# RP2040-mini_4L.net
KiCad netlist of a schematic drawn in EAGLE
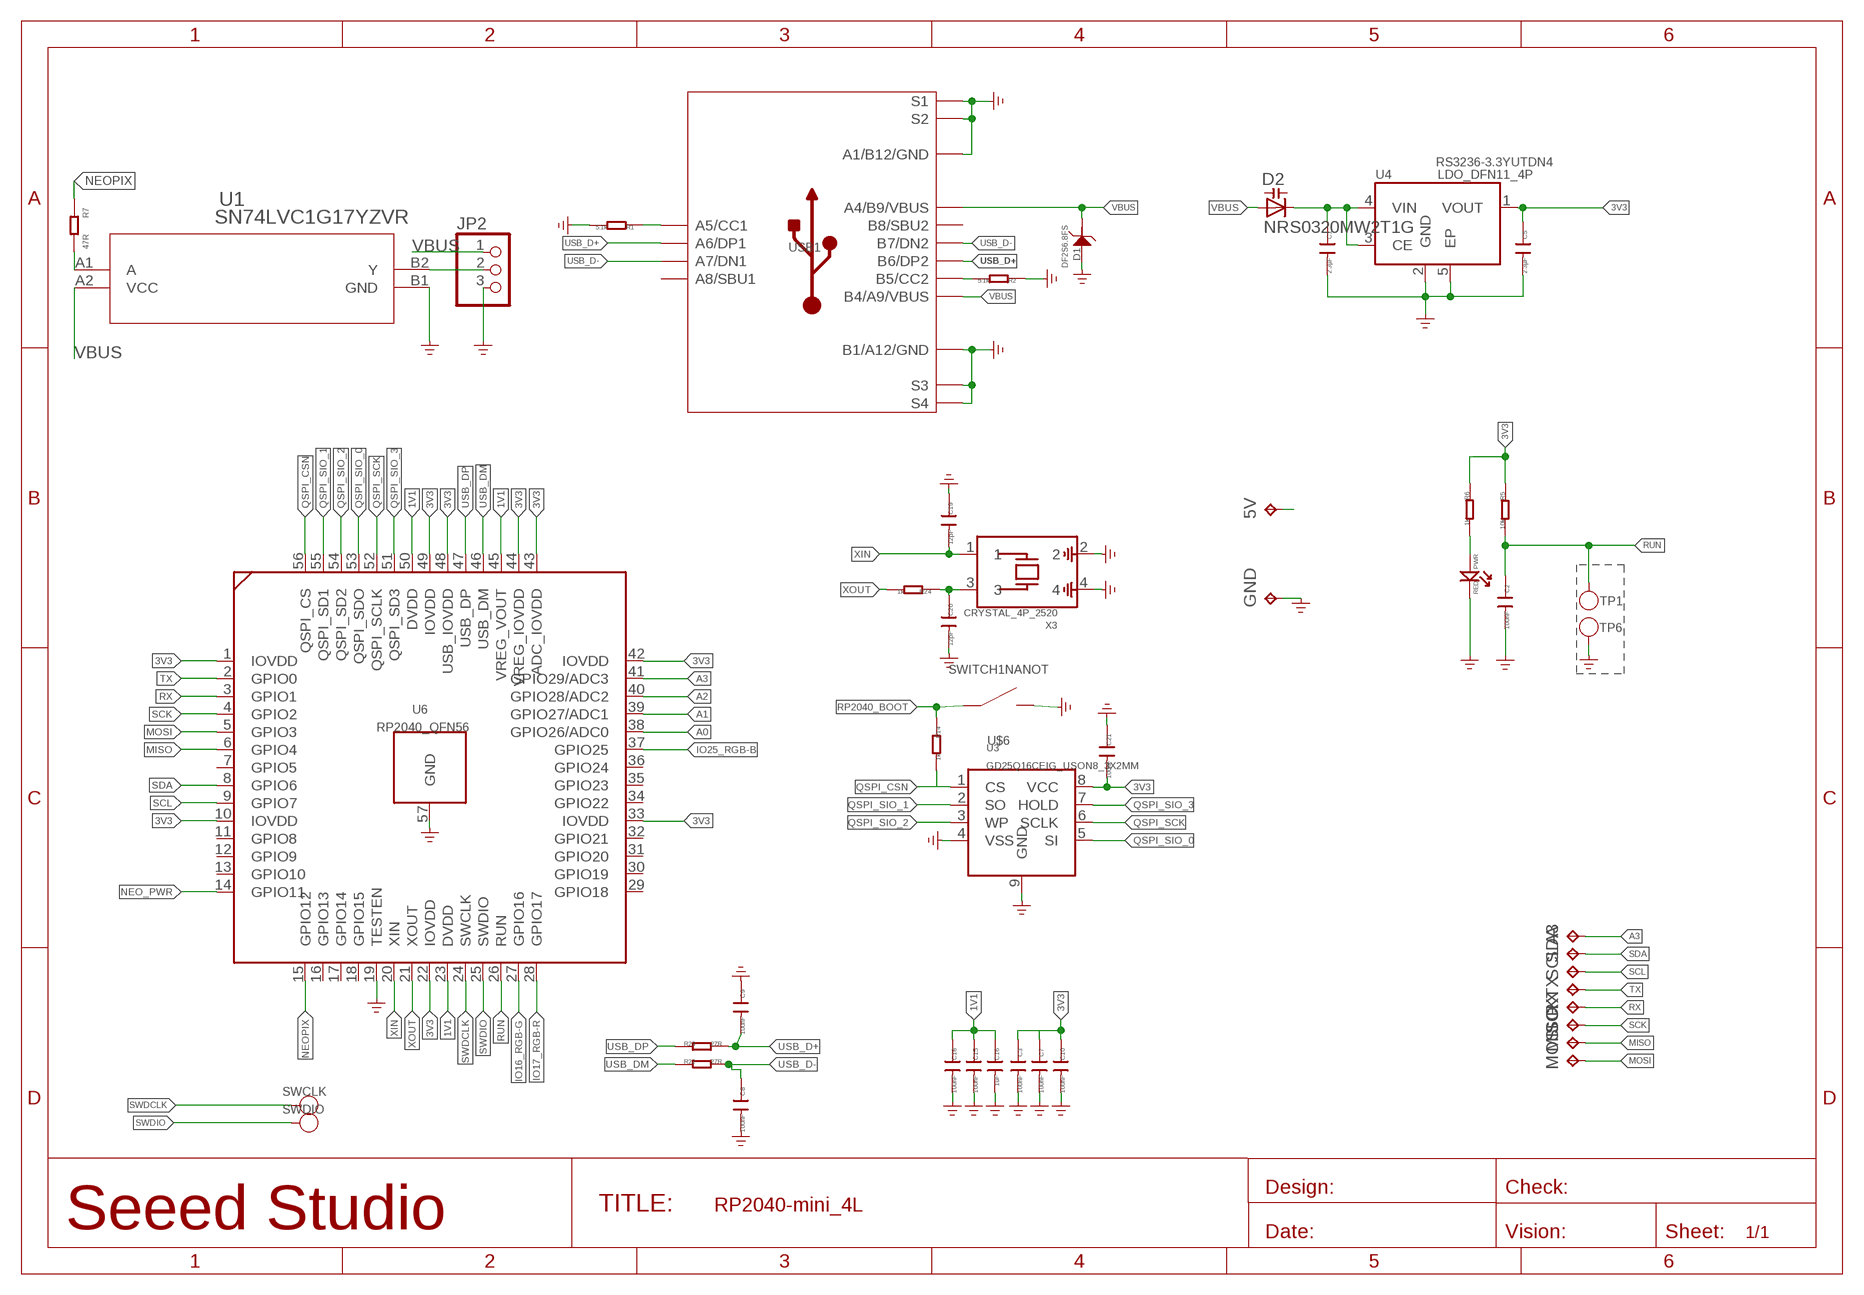
[diagram p0: schematic, sheet 1]

(export (version "E")
  (design (tool "Eeschema 10.0.6"))
  (components
    (comp (ref "5V")
      (value "TPTP09R")
      (footprint "eagle-import:TP09R")
      (libsource (lib "eagle-import") (part "TPTP09R"))
    )
    (comp (ref "A3")
      (value "TPTP07R")
      (footprint "eagle-import:TP07R")
      (libsource (lib "eagle-import") (part "TPTP07R"))
    )
    (comp (ref "C1")
      (value "2.3µF")
      (footprint "eagle-import:0201_NORMAL_NOSILK")
      (libsource (lib "eagle-import") (part "CAP{backslash}0201NNS"))
    )
    (comp (ref "C2")
      (value "100nF")
      (footprint "eagle-import:0201_NORMAL_NOSILK")
      (libsource (lib "eagle-import") (part "CAP{backslash}0201NNS"))
    )
    (comp (ref "C3")
      (value "100nF")
      (footprint "eagle-import:0201_NORMAL_NOSILK")
      (libsource (lib "eagle-import") (part "CAP{backslash}0201NNS"))
    )
    (comp (ref "C5")
      (value "2.3µF")
      (footprint "eagle-import:0201_NORMAL_NOSILK")
      (libsource (lib "eagle-import") (part "CAP{backslash}0201NNS"))
    )
    (comp (ref "C7")
      (value "100nF")
      (footprint "eagle-import:0201_NORMAL_NOSILK")
      (libsource (lib "eagle-import") (part "CAP{backslash}0201NNS"))
    )
    (comp (ref "C8")
      (value "100nF")
      (footprint "eagle-import:0201_NORMAL_NOSILK")
      (libsource (lib "eagle-import") (part "CAP{backslash}0201NNS"))
    )
    (comp (ref "C9")
      (value "100nF")
      (footprint "eagle-import:0201_NORMAL_NOSILK")
      (libsource (lib "eagle-import") (part "CAP{backslash}0201NNS"))
    )
    (comp (ref "C10")
      (value "100nF")
      (footprint "eagle-import:0201_NORMAL_NOSILK")
      (libsource (lib "eagle-import") (part "CAP{backslash}0201NNS"))
    )
    (comp (ref "C15")
      (value "100nF")
      (footprint "eagle-import:0201_NORMAL_NOSILK")
      (libsource (lib "eagle-import") (part "CAP{backslash}0201NNS"))
    )
    (comp (ref "C16")
      (value "1uF")
      (footprint "eagle-import:0201_NORMAL_NOSILK")
      (libsource (lib "eagle-import") (part "CAP{backslash}0201NNS"))
    )
    (comp (ref "C18")
      (value "100nF")
      (footprint "eagle-import:0201_NORMAL_NOSILK")
      (libsource (lib "eagle-import") (part "CAP{backslash}0201NNS"))
    )
    (comp (ref "C19")
      (value "12pF")
      (footprint "eagle-import:0201_NORMAL_NOSILK")
      (libsource (lib "eagle-import") (part "CAP{backslash}0201NNS"))
    )
    (comp (ref "C20")
      (value "12pF")
      (footprint "eagle-import:0201_NORMAL_NOSILK")
      (libsource (lib "eagle-import") (part "CAP{backslash}0201NNS"))
    )
    (comp (ref "C21")
      (value "100nF")
      (footprint "eagle-import:0201_NORMAL_NOSILK")
      (libsource (lib "eagle-import") (part "CAP{backslash}0201NNS"))
    )
    (comp (ref "D1")
      (value "DF2S6.8FS")
      (footprint "eagle-import:SOD-923")
      (libsource (lib "eagle-import") (part "D-ESD-2P'DF2S6.8FS'"))
    )
    (comp (ref "D2")
      (value "NRS0320MW2T1G")
      (footprint "eagle-import:SOD523")
      (libsource (lib "eagle-import") (part "DIODE_CAPACITANCE-SOD523"))
    )
    (comp (ref "GND")
      (value "TPTP09R")
      (footprint "eagle-import:TP09R")
      (libsource (lib "eagle-import") (part "TPTP09R"))
    )
    (comp (ref "JP2")
      (value "PINHD-1X3")
      (footprint "eagle-import:1X03")
      (libsource (lib "eagle-import") (part "PINHD-1X3"))
    )
    (comp (ref "MISO")
      (value "TPTP07R")
      (footprint "eagle-import:TP07R")
      (libsource (lib "eagle-import") (part "TPTP07R"))
    )
    (comp (ref "MOSI")
      (value "TPTP07R")
      (footprint "eagle-import:TP07R")
      (libsource (lib "eagle-import") (part "TPTP07R"))
    )
    (comp (ref "PWR")
      (value "RED")
      (footprint "eagle-import:LED-0402")
      (libsource (lib "eagle-import") (part "LED-0402"))
    )
    (comp (ref "R1")
      (value "5.1k")
      (footprint "eagle-import:R0201")
      (libsource (lib "eagle-import") (part "R-0201"))
    )
    (comp (ref "R2")
      (value "5.1k")
      (footprint "eagle-import:R0201")
      (libsource (lib "eagle-import") (part "R-0201"))
    )
    (comp (ref "R5")
      (value "10k")
      (footprint "eagle-import:R0201")
      (libsource (lib "eagle-import") (part "R-0201"))
    )
    (comp (ref "R6")
      (value "1k")
      (footprint "eagle-import:R0201")
      (libsource (lib "eagle-import") (part "R-0201"))
    )
    (comp (ref "R7")
      (value "47R")
      (footprint "eagle-import:R0201")
      (libsource (lib "eagle-import") (part "RES-0201"))
    )
    (comp (ref "R14")
      (value "1k")
      (footprint "eagle-import:R0201")
      (libsource (lib "eagle-import") (part "R-0201"))
    )
    (comp (ref "R22")
      (value "27R")
      (footprint "eagle-import:R0201")
      (libsource (lib "eagle-import") (part "R-0201"))
    )
    (comp (ref "R23")
      (value "27R")
      (footprint "eagle-import:R0201")
      (libsource (lib "eagle-import") (part "R-0201"))
    )
    (comp (ref "R24")
      (value "1k")
      (footprint "eagle-import:R0201")
      (libsource (lib "eagle-import") (part "R-0201"))
    )
    (comp (ref "RX")
      (value "TPTP07R")
      (footprint "eagle-import:TP07R")
      (libsource (lib "eagle-import") (part "TPTP07R"))
    )
    (comp (ref "SCK")
      (value "TPTP07R")
      (footprint "eagle-import:TP07R")
      (libsource (lib "eagle-import") (part "TPTP07R"))
    )
    (comp (ref "SCL")
      (value "TPTP07R")
      (footprint "eagle-import:TP07R")
      (libsource (lib "eagle-import") (part "TPTP07R"))
    )
    (comp (ref "SDA")
      (value "TPTP07R")
      (footprint "eagle-import:TP07R")
      (libsource (lib "eagle-import") (part "TPTP07R"))
    )
    (comp (ref "SWCLK")
      (value "TEST-POINT-35")
      (footprint "eagle-import:TP_3535")
      (libsource (lib "eagle-import") (part "TEST-POINT-35"))
    )
    (comp (ref "SWDIO")
      (value "TEST-POINT-35")
      (footprint "eagle-import:TP_3535")
      (libsource (lib "eagle-import") (part "TEST-POINT-35"))
    )
    (comp (ref "TP1")
      (value "TEST-POINT-35")
      (footprint "eagle-import:TP_3535")
      (libsource (lib "eagle-import") (part "TEST-POINT-35"))
    )
    (comp (ref "TP6")
      (value "TEST-POINT-35")
      (footprint "eagle-import:TP_3535")
      (libsource (lib "eagle-import") (part "TEST-POINT-35"))
    )
    (comp (ref "TX")
      (value "TPTP07R")
      (footprint "eagle-import:TP07R")
      (libsource (lib "eagle-import") (part "TPTP07R"))
    )
    (comp (ref "U$6")
      (value "SWITCH1NANOT")
      (footprint "eagle-import:NANOT")
      (libsource (lib "eagle-import") (part "SWITCH1NANOT"))
    )
    (comp (ref "U1")
      (value "SN74LVC1G17YZVR")
      (footprint "eagle-import:YZV4")
      (fields (field (name "COPYRIGHT") "Copyright (C) 2024 Ultra Librarian. All rights reserved."))
      (libsource (lib "eagle-import") (part "SN74LVC1G17YZVR"))
    )
    (comp (ref "U3")
      (value "GD25Q16CEIG_USON8_3X2MM")
      (footprint "eagle-import:GD25Q16CEIG_USON8_3X2MM")
      (libsource (lib "eagle-import") (part "GD25Q16CEIG_USON8_3X2MM"))
    )
    (comp (ref "U4")
      (value "LDO_DFN11_4P")
      (footprint "eagle-import:LDO_DFN1_1_4P")
      (libsource (lib "eagle-import") (part "LDO_DFN11_4P"))
    )
    (comp (ref "U6")
      (value "RP2040_QFN56")
      (footprint "eagle-import:RP2040_QFN56")
      (libsource (lib "eagle-import") (part "RP2040_QFN56"))
    )
    (comp (ref "USB1")
      (value "USB2.0-TYPE-C")
      (footprint "eagle-import:USB2.0-TYPE-C")
      (libsource (lib "eagle-import") (part "USB2.0-TYPE-C"))
    )
    (comp (ref "X3")
      (value "CRYSTAL_4P_2520")
      (footprint "eagle-import:CRYSTAL_4P_2520")
      (libsource (lib "eagle-import") (part "CRYSTAL_4P_2520"))
    )
  )
  (nets
    (net (code "1") (name "1V1") (class "Default")
      (node (ref "C15") (pin "1") (pinfunction "1_1") (pintype "passive"))
      (node (ref "C16") (pin "1") (pinfunction "1_1") (pintype "passive"))
      (node (ref "C18") (pin "1") (pinfunction "1_1") (pintype "passive"))
      (node (ref "U6") (pin "23") (pinfunction "DVDD_23") (pintype "bidirectional"))
      (node (ref "U6") (pin "45") (pinfunction "VREG_VOUT_45") (pintype "bidirectional"))
      (node (ref "U6") (pin "50") (pinfunction "DVDD_50") (pintype "bidirectional"))
    )
    (net (code "2") (name "3V3") (class "Default")
      (node (ref "C10") (pin "1") (pinfunction "1_1") (pintype "passive"))
      (node (ref "C21") (pin "2") (pinfunction "2_2") (pintype "passive"))
      (node (ref "C3") (pin "1") (pinfunction "1_1") (pintype "passive"))
      (node (ref "C5") (pin "1") (pinfunction "1_1") (pintype "passive"))
      (node (ref "C7") (pin "1") (pinfunction "1_1") (pintype "passive"))
      (node (ref "R5") (pin "1") (pinfunction "1_1") (pintype "passive"))
      (node (ref "R6") (pin "1") (pinfunction "1_1") (pintype "passive"))
      (node (ref "U3") (pin "8") (pinfunction "VCC_8") (pintype "bidirectional"))
      (node (ref "U4") (pin "1") (pinfunction "VOUT_1") (pintype "bidirectional"))
      (node (ref "U6") (pin "1") (pinfunction "IOVDD_1") (pintype "bidirectional"))
      (node (ref "U6") (pin "10") (pinfunction "IOVDD_10") (pintype "bidirectional"))
      (node (ref "U6") (pin "22") (pinfunction "IOVDD_22") (pintype "bidirectional"))
      (node (ref "U6") (pin "33") (pinfunction "IOVDD_33") (pintype "bidirectional"))
      (node (ref "U6") (pin "42") (pinfunction "IOVDD_42") (pintype "bidirectional"))
      (node (ref "U6") (pin "43") (pinfunction "ADC_IOVDD_43") (pintype "bidirectional"))
      (node (ref "U6") (pin "44") (pinfunction "VREG_IOVDD_44") (pintype "bidirectional"))
      (node (ref "U6") (pin "48") (pinfunction "USB_IOVDD_48") (pintype "bidirectional"))
      (node (ref "U6") (pin "49") (pinfunction "IOVDD_49") (pintype "bidirectional"))
    )
    (net (code "3") (name "A0") (class "Default")
      (node (ref "U6") (pin "38") (pinfunction "GPIO26/ADC0_38") (pintype "bidirectional"))
    )
    (net (code "4") (name "A1") (class "Default")
      (node (ref "U6") (pin "39") (pinfunction "GPIO27/ADC1_39") (pintype "bidirectional"))
    )
    (net (code "5") (name "A2") (class "Default")
      (node (ref "U6") (pin "40") (pinfunction "GPIO28/ADC2_40") (pintype "bidirectional"))
    )
    (net (code "6") (name "A3") (class "Default")
      (node (ref "A3") (pin "TP") (pinfunction "TP_TP") (pintype "input"))
      (node (ref "U6") (pin "41") (pinfunction "GPIO29/ADC3_41") (pintype "bidirectional"))
    )
    (net (code "7") (name "GND_POWER") (class "Default")
      (node (ref "C1") (pin "2") (pinfunction "2_2") (pintype "passive"))
      (node (ref "C10") (pin "2") (pinfunction "2_2") (pintype "passive"))
      (node (ref "C15") (pin "2") (pinfunction "2_2") (pintype "passive"))
      (node (ref "C16") (pin "2") (pinfunction "2_2") (pintype "passive"))
      (node (ref "C18") (pin "2") (pinfunction "2_2") (pintype "passive"))
      (node (ref "C19") (pin "1") (pinfunction "1_1") (pintype "passive"))
      (node (ref "C2") (pin "2") (pinfunction "2_2") (pintype "passive"))
      (node (ref "C20") (pin "2") (pinfunction "2_2") (pintype "passive"))
      (node (ref "C21") (pin "1") (pinfunction "1_1") (pintype "passive"))
      (node (ref "C3") (pin "2") (pinfunction "2_2") (pintype "passive"))
      (node (ref "C5") (pin "2") (pinfunction "2_2") (pintype "passive"))
      (node (ref "C7") (pin "2") (pinfunction "2_2") (pintype "passive"))
      (node (ref "C8") (pin "2") (pinfunction "2_2") (pintype "passive"))
      (node (ref "C9") (pin "1") (pinfunction "1_1") (pintype "passive"))
      (node (ref "D1") (pin "2") (pinfunction "1_2") (pintype "bidirectional"))
      (node (ref "GND") (pin "TP") (pinfunction "TP_TP") (pintype "input"))
      (node (ref "JP2") (pin "3") (pinfunction "3_3") (pintype "passive"))
      (node (ref "PWR") (pin "-") (pinfunction "-_-") (pintype "passive"))
      (node (ref "R1") (pin "2") (pinfunction "2_2") (pintype "passive"))
      (node (ref "R2") (pin "1") (pinfunction "1_1") (pintype "passive"))
      (node (ref "TP6") (pin "T") (pinfunction "T_T") (pintype "bidirectional"))
      (node (ref "U$6") (pin "2") (pinfunction "B_2") (pintype "bidirectional"))
      (node (ref "U1") (pin "B1") (pinfunction "GND_B1") (pintype "power_in"))
      (node (ref "U3") (pin "4") (pinfunction "VSS_4") (pintype "bidirectional"))
      (node (ref "U3") (pin "9") (pinfunction "GND_9") (pintype "bidirectional"))
      (node (ref "U4") (pin "2") (pinfunction "GND_2") (pintype "bidirectional"))
      (node (ref "U4") (pin "5") (pinfunction "EP_5") (pintype "bidirectional"))
      (node (ref "U6") (pin "19") (pinfunction "TESTEN_19") (pintype "bidirectional"))
      (node (ref "U6") (pin "57") (pinfunction "GND_57") (pintype "bidirectional"))
      (node (ref "USB1") (pin "A1_B12") (pinfunction "A1/B12/GND_A1_B12") (pintype "bidirectional"))
      (node (ref "USB1") (pin "B1_A12") (pinfunction "B1/A12/GND_B1_A12") (pintype "bidirectional"))
      (node (ref "USB1") (pin "S1") (pinfunction "S1_S1") (pintype "bidirectional"))
      (node (ref "USB1") (pin "S2") (pinfunction "S2_S2") (pintype "bidirectional"))
      (node (ref "USB1") (pin "S3") (pinfunction "S3_S3") (pintype "bidirectional"))
      (node (ref "USB1") (pin "S4") (pinfunction "S4_S4") (pintype "bidirectional"))
      (node (ref "USB1") (pin "S5") (pinfunction "S1_S5") (pintype "bidirectional"))
      (node (ref "USB1") (pin "S6") (pinfunction "S2_S6") (pintype "bidirectional"))
      (node (ref "X3") (pin "2") (pinfunction "2_2") (pintype "bidirectional"))
      (node (ref "X3") (pin "4") (pinfunction "4_4") (pintype "bidirectional"))
    )
    (net (code "8") (name "IO16_RGB-G") (class "Default")
      (node (ref "U6") (pin "27") (pinfunction "GPIO16_27") (pintype "bidirectional"))
    )
    (net (code "9") (name "IO17_RGB-R") (class "Default")
      (node (ref "U6") (pin "28") (pinfunction "GPIO17_28") (pintype "bidirectional"))
    )
    (net (code "10") (name "IO25_RGB-B") (class "Default")
      (node (ref "U6") (pin "37") (pinfunction "GPIO25_37") (pintype "bidirectional"))
    )
    (net (code "11") (name "MISO") (class "Default")
      (node (ref "MISO") (pin "TP") (pinfunction "TP_TP") (pintype "input"))
      (node (ref "U6") (pin "6") (pinfunction "GPIO4_6") (pintype "bidirectional"))
    )
    (net (code "12") (name "MOSI") (class "Default")
      (node (ref "MOSI") (pin "TP") (pinfunction "TP_TP") (pintype "input"))
      (node (ref "U6") (pin "5") (pinfunction "GPIO3_5") (pintype "bidirectional"))
    )
    (net (code "13") (name "NEOPIX") (class "Default")
      (node (ref "R7") (pin "2") (pinfunction "2_2") (pintype "passive"))
      (node (ref "U6") (pin "15") (pinfunction "GPIO12_15") (pintype "bidirectional"))
    )
    (net (code "14") (name "NEO_PWR") (class "Default")
      (node (ref "U6") (pin "14") (pinfunction "GPIO11_14") (pintype "bidirectional"))
    )
    (net (code "15") (name "Net-(C20-Pad1)") (class "Default")
      (node (ref "C20") (pin "1") (pinfunction "1_1") (pintype "passive"))
      (node (ref "R24") (pin "1") (pinfunction "1_1") (pintype "passive"))
      (node (ref "X3") (pin "3") (pinfunction "3_3") (pintype "bidirectional"))
    )
    (net (code "16") (name "Net-(PWR-Pad+)") (class "Default")
      (node (ref "PWR") (pin "+") (pinfunction "+_+") (pintype "passive"))
      (node (ref "R6") (pin "2") (pinfunction "2_2") (pintype "passive"))
    )
    (net (code "17") (name "Net-(U1-A)") (class "Default")
      (node (ref "R7") (pin "1") (pinfunction "1_1") (pintype "passive"))
      (node (ref "U1") (pin "A1") (pinfunction "A_A1") (pintype "input"))
    )
    (net (code "18") (name "Net-(U1-Y)") (class "Default")
      (node (ref "JP2") (pin "2") (pinfunction "2_2") (pintype "passive"))
      (node (ref "U1") (pin "B2") (pinfunction "Y_B2") (pintype "output"))
    )
    (net (code "19") (name "Net-(U4-CE)") (class "Default")
      (node (ref "C1") (pin "1") (pinfunction "1_1") (pintype "passive"))
      (node (ref "D2") (pin "C") (pinfunction "C_C") (pintype "passive"))
      (node (ref "U4") (pin "3") (pinfunction "CE_3") (pintype "bidirectional"))
      (node (ref "U4") (pin "4") (pinfunction "VIN_4") (pintype "bidirectional"))
    )
    (net (code "20") (name "Net-(USB1-A5{slash}CC1)") (class "Default")
      (node (ref "R1") (pin "1") (pinfunction "1_1") (pintype "passive"))
      (node (ref "USB1") (pin "A5") (pinfunction "A5/CC1_A5") (pintype "bidirectional"))
    )
    (net (code "21") (name "Net-(USB1-B5{slash}CC2)") (class "Default")
      (node (ref "R2") (pin "2") (pinfunction "2_2") (pintype "passive"))
      (node (ref "USB1") (pin "B5") (pinfunction "B5/CC2_B5") (pintype "bidirectional"))
    )
    (net (code "22") (name "QSPI_CSN") (class "Default")
      (node (ref "R14") (pin "2") (pinfunction "2_2") (pintype "passive"))
      (node (ref "U3") (pin "1") (pinfunction "CS_1") (pintype "bidirectional"))
      (node (ref "U6") (pin "56") (pinfunction "QSPI_CS_56") (pintype "bidirectional"))
    )
    (net (code "23") (name "QSPI_SCK") (class "Default")
      (node (ref "U3") (pin "6") (pinfunction "SCLK_6") (pintype "bidirectional"))
      (node (ref "U6") (pin "52") (pinfunction "QSPI_SCLK_52") (pintype "bidirectional"))
    )
    (net (code "24") (name "QSPI_SIO_0") (class "Default")
      (node (ref "U3") (pin "5") (pinfunction "SI_5") (pintype "bidirectional"))
      (node (ref "U6") (pin "53") (pinfunction "QSPI_SDO_53") (pintype "bidirectional"))
    )
    (net (code "25") (name "QSPI_SIO_1") (class "Default")
      (node (ref "U3") (pin "2") (pinfunction "SO_2") (pintype "bidirectional"))
      (node (ref "U6") (pin "55") (pinfunction "QSPI_SD1_55") (pintype "bidirectional"))
    )
    (net (code "26") (name "QSPI_SIO_2") (class "Default")
      (node (ref "U3") (pin "3") (pinfunction "WP_3") (pintype "bidirectional"))
      (node (ref "U6") (pin "54") (pinfunction "QSPI_SD2_54") (pintype "bidirectional"))
    )
    (net (code "27") (name "QSPI_SIO_3") (class "Default")
      (node (ref "U3") (pin "7") (pinfunction "HOLD_7") (pintype "bidirectional"))
      (node (ref "U6") (pin "51") (pinfunction "QSPI_SD3_51") (pintype "bidirectional"))
    )
    (net (code "28") (name "RP2040_BOOT") (class "Default")
      (node (ref "R14") (pin "1") (pinfunction "1_1") (pintype "passive"))
      (node (ref "U$6") (pin "1") (pinfunction "A_1") (pintype "bidirectional"))
    )
    (net (code "29") (name "RUN") (class "Default")
      (node (ref "C2") (pin "1") (pinfunction "1_1") (pintype "passive"))
      (node (ref "R5") (pin "2") (pinfunction "2_2") (pintype "passive"))
      (node (ref "TP1") (pin "T") (pinfunction "T_T") (pintype "bidirectional"))
      (node (ref "U6") (pin "26") (pinfunction "RUN_26") (pintype "bidirectional"))
    )
    (net (code "30") (name "RX") (class "Default")
      (node (ref "RX") (pin "TP") (pinfunction "TP_TP") (pintype "input"))
      (node (ref "U6") (pin "3") (pinfunction "GPIO1_3") (pintype "bidirectional"))
    )
    (net (code "31") (name "SCK") (class "Default")
      (node (ref "SCK") (pin "TP") (pinfunction "TP_TP") (pintype "input"))
      (node (ref "U6") (pin "4") (pinfunction "GPIO2_4") (pintype "bidirectional"))
    )
    (net (code "32") (name "SCL") (class "Default")
      (node (ref "SCL") (pin "TP") (pinfunction "TP_TP") (pintype "input"))
      (node (ref "U6") (pin "9") (pinfunction "GPIO7_9") (pintype "bidirectional"))
    )
    (net (code "33") (name "SDA") (class "Default")
      (node (ref "SDA") (pin "TP") (pinfunction "TP_TP") (pintype "input"))
      (node (ref "U6") (pin "8") (pinfunction "GPIO6_8") (pintype "bidirectional"))
    )
    (net (code "34") (name "SWDCLK") (class "Default")
      (node (ref "SWCLK") (pin "T") (pinfunction "T_T") (pintype "bidirectional"))
      (node (ref "U6") (pin "24") (pinfunction "SWCLK_24") (pintype "bidirectional"))
    )
    (net (code "35") (name "SWDIO") (class "Default")
      (node (ref "SWDIO") (pin "T") (pinfunction "T_T") (pintype "bidirectional"))
      (node (ref "U6") (pin "25") (pinfunction "SWDIO_25") (pintype "bidirectional"))
    )
    (net (code "36") (name "TX") (class "Default")
      (node (ref "TX") (pin "TP") (pinfunction "TP_TP") (pintype "input"))
      (node (ref "U6") (pin "2") (pinfunction "GPIO0_2") (pintype "bidirectional"))
    )
    (net (code "37") (name "USB_D+") (class "Default")
      (node (ref "C9") (pin "2") (pinfunction "2_2") (pintype "passive"))
      (node (ref "R23") (pin "2") (pinfunction "2_2") (pintype "passive"))
      (node (ref "USB1") (pin "A6") (pinfunction "A6/DP1_A6") (pintype "bidirectional"))
      (node (ref "USB1") (pin "B6") (pinfunction "B6/DP2_B6") (pintype "bidirectional"))
    )
    (net (code "38") (name "USB_D-") (class "Default")
      (node (ref "C8") (pin "1") (pinfunction "1_1") (pintype "passive"))
      (node (ref "R22") (pin "2") (pinfunction "2_2") (pintype "passive"))
      (node (ref "USB1") (pin "A7") (pinfunction "A7/DN1_A7") (pintype "bidirectional"))
      (node (ref "USB1") (pin "B7") (pinfunction "B7/DN2_B7") (pintype "bidirectional"))
    )
    (net (code "39") (name "USB_DM") (class "Default")
      (node (ref "R22") (pin "1") (pinfunction "1_1") (pintype "passive"))
      (node (ref "U6") (pin "46") (pinfunction "USB_DM_46") (pintype "bidirectional"))
    )
    (net (code "40") (name "USB_DP") (class "Default")
      (node (ref "R23") (pin "1") (pinfunction "1_1") (pintype "passive"))
      (node (ref "U6") (pin "47") (pinfunction "USB_DP_47") (pintype "bidirectional"))
    )
    (net (code "41") (name "VBUS") (class "Default")
      (node (ref "5V") (pin "TP") (pinfunction "TP_TP") (pintype "input"))
      (node (ref "D1") (pin "1") (pinfunction "2_1") (pintype "bidirectional"))
      (node (ref "D2") (pin "A") (pinfunction "A_A") (pintype "passive"))
      (node (ref "JP2") (pin "1") (pinfunction "1_1") (pintype "passive"))
      (node (ref "U1") (pin "A2") (pinfunction "VCC_A2") (pintype "power_in"))
      (node (ref "USB1") (pin "A4_B9") (pinfunction "A4/B9/VBUS_A4_B9") (pintype "bidirectional"))
      (node (ref "USB1") (pin "B4_A9") (pinfunction "B4/A9/VBUS_B4_A9") (pintype "bidirectional"))
    )
    (net (code "42") (name "XIN") (class "Default")
      (node (ref "C19") (pin "2") (pinfunction "2_2") (pintype "passive"))
      (node (ref "U6") (pin "20") (pinfunction "XIN_20") (pintype "bidirectional"))
      (node (ref "X3") (pin "1") (pinfunction "1_1") (pintype "bidirectional"))
    )
    (net (code "43") (name "XOUT") (class "Default")
      (node (ref "R24") (pin "2") (pinfunction "2_2") (pintype "passive"))
      (node (ref "U6") (pin "21") (pinfunction "XOUT_21") (pintype "bidirectional"))
    )
    (net (code "44") (name "unconnected-(U6-GPIO5-Pad7)") (class "Default")
      (node (ref "U6") (pin "7") (pinfunction "GPIO5_7") (pintype "bidirectional"))
    )
    (net (code "45") (name "unconnected-(U6-GPIO8-Pad11)") (class "Default")
      (node (ref "U6") (pin "11") (pinfunction "GPIO8_11") (pintype "bidirectional"))
    )
    (net (code "46") (name "unconnected-(U6-GPIO9-Pad12)") (class "Default")
      (node (ref "U6") (pin "12") (pinfunction "GPIO9_12") (pintype "bidirectional"))
    )
    (net (code "47") (name "unconnected-(U6-GPIO10-Pad13)") (class "Default")
      (node (ref "U6") (pin "13") (pinfunction "GPIO10_13") (pintype "bidirectional"))
    )
    (net (code "48") (name "unconnected-(U6-GPIO13-Pad16)") (class "Default")
      (node (ref "U6") (pin "16") (pinfunction "GPIO13_16") (pintype "bidirectional"))
    )
    (net (code "49") (name "unconnected-(U6-GPIO14-Pad17)") (class "Default")
      (node (ref "U6") (pin "17") (pinfunction "GPIO14_17") (pintype "bidirectional"))
    )
    (net (code "50") (name "unconnected-(U6-GPIO15-Pad18)") (class "Default")
      (node (ref "U6") (pin "18") (pinfunction "GPIO15_18") (pintype "bidirectional"))
    )
    (net (code "51") (name "unconnected-(U6-GPIO18-Pad29)") (class "Default")
      (node (ref "U6") (pin "29") (pinfunction "GPIO18_29") (pintype "bidirectional"))
    )
    (net (code "52") (name "unconnected-(U6-GPIO19-Pad30)") (class "Default")
      (node (ref "U6") (pin "30") (pinfunction "GPIO19_30") (pintype "bidirectional"))
    )
    (net (code "53") (name "unconnected-(U6-GPIO20-Pad31)") (class "Default")
      (node (ref "U6") (pin "31") (pinfunction "GPIO20_31") (pintype "bidirectional"))
    )
    (net (code "54") (name "unconnected-(U6-GPIO21-Pad32)") (class "Default")
      (node (ref "U6") (pin "32") (pinfunction "GPIO21_32") (pintype "bidirectional"))
    )
    (net (code "55") (name "unconnected-(U6-GPIO22-Pad34)") (class "Default")
      (node (ref "U6") (pin "34") (pinfunction "GPIO22_34") (pintype "bidirectional"))
    )
    (net (code "56") (name "unconnected-(U6-GPIO23-Pad35)") (class "Default")
      (node (ref "U6") (pin "35") (pinfunction "GPIO23_35") (pintype "bidirectional"))
    )
    (net (code "57") (name "unconnected-(U6-GPIO24-Pad36)") (class "Default")
      (node (ref "U6") (pin "36") (pinfunction "GPIO24_36") (pintype "bidirectional"))
    )
    (net (code "58") (name "unconnected-(USB1-A8{slash}SBU1-PadA8)") (class "Default")
      (node (ref "USB1") (pin "A8") (pinfunction "A8/SBU1_A8") (pintype "bidirectional"))
    )
    (net (code "59") (name "unconnected-(USB1-B8{slash}SBU2-PadB8)") (class "Default")
      (node (ref "USB1") (pin "B8") (pinfunction "B8/SBU2_B8") (pintype "bidirectional"))
    )
  )
)
